# envelope_follower_1.net
KiCad netlist of a schematic drawn in EAGLE
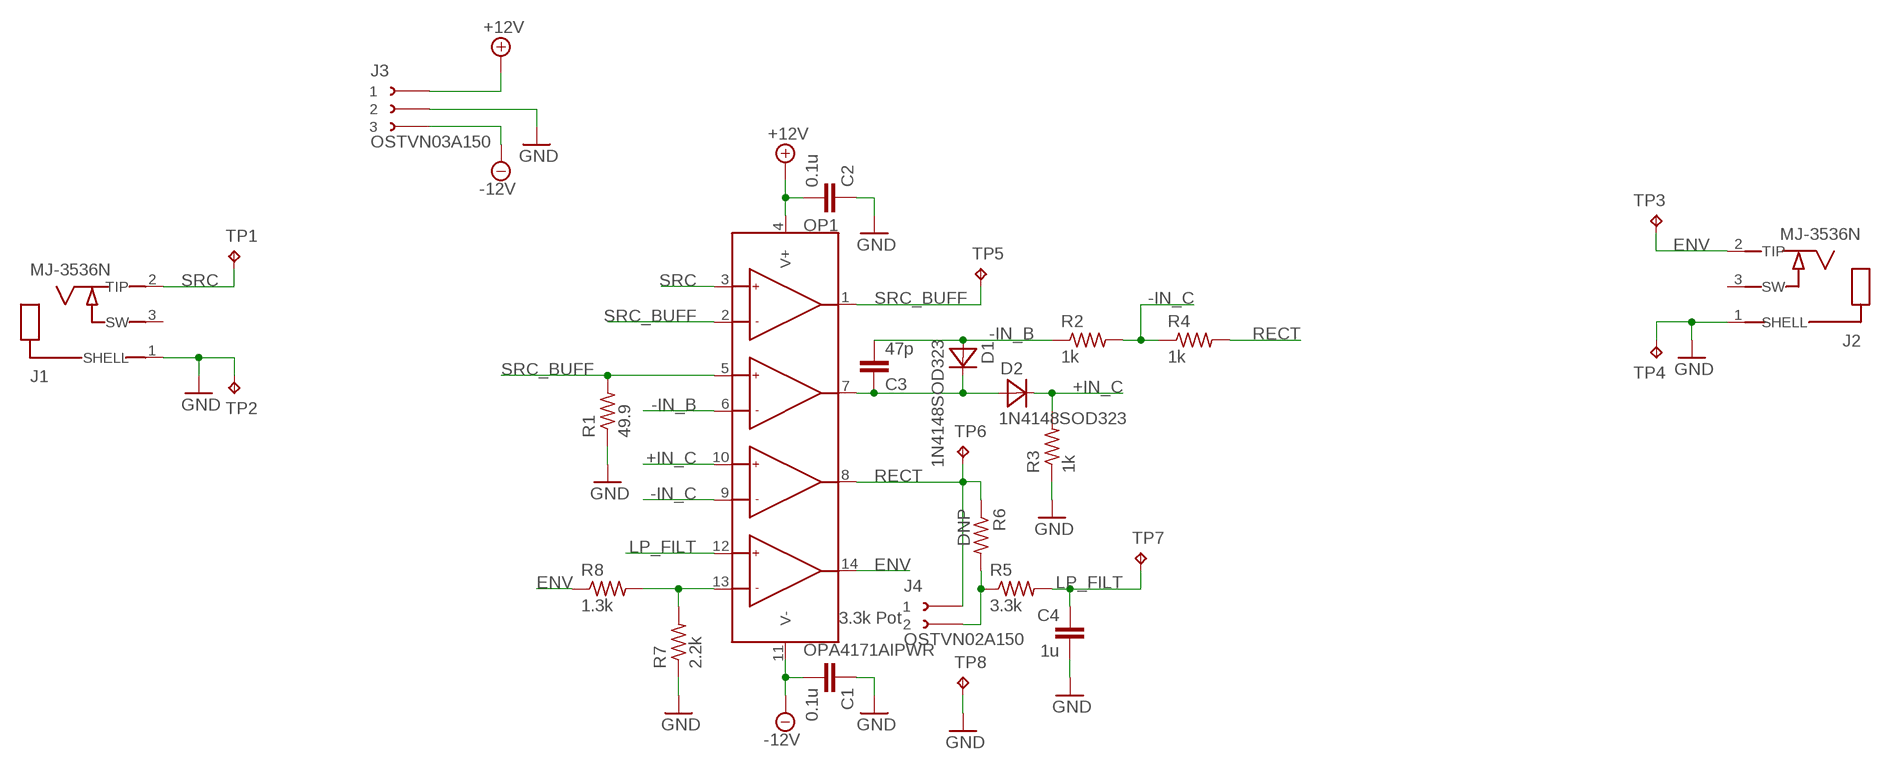
[diagram p0: schematic, sheet 1]

(export (version "E")
  (design (tool "Eeschema 10.0.6"))
  (components
    (comp (ref "C1")
      (value "0.1u")
      (footprint "eagle-import:C0603")
      (libsource (lib "eagle-import") (part "CAP-CER-SMD0603"))
    )
    (comp (ref "C2")
      (value "0.1u")
      (footprint "eagle-import:C0603")
      (libsource (lib "eagle-import") (part "CAP-CER-SMD0603"))
    )
    (comp (ref "C3")
      (value "47p")
      (footprint "eagle-import:C0603")
      (libsource (lib "eagle-import") (part "CAP-CER-SMD0603"))
    )
    (comp (ref "C4")
      (value "1u")
      (footprint "eagle-import:C0603")
      (libsource (lib "eagle-import") (part "CAP-CER-SMD0603"))
    )
    (comp (ref "D1")
      (value "1N4148SOD323")
      (footprint "eagle-import:SOD323")
      (libsource (lib "eagle-import") (part "1N4148SOD323"))
    )
    (comp (ref "D2")
      (value "1N4148SOD323")
      (footprint "eagle-import:SOD323")
      (libsource (lib "eagle-import") (part "1N4148SOD323"))
    )
    (comp (ref "J1")
      (value "MJ-3536N")
      (footprint "eagle-import:MJ-3536N")
      (libsource (lib "eagle-import") (part "MJ-3536N"))
    )
    (comp (ref "J2")
      (value "MJ-3536N")
      (footprint "eagle-import:MJ-3536N")
      (libsource (lib "eagle-import") (part "MJ-3536N"))
    )
    (comp (ref "J3")
      (value "OSTVN03A150")
      (footprint "eagle-import:OSTVN03A150")
      (libsource (lib "eagle-import") (part "OSTVN03A150"))
    )
    (comp (ref "J4")
      (value "OSTVN02A150")
      (footprint "eagle-import:OSTVN02A150")
      (libsource (lib "eagle-import") (part "OSTVN02A150"))
    )
    (comp (ref "OP1")
      (value "OPA4171AIPWR")
      (footprint "eagle-import:SOP65P640X120-14")
      (libsource (lib "eagle-import") (part "OPA4171AIPWR"))
    )
    (comp (ref "R1")
      (value "49.9")
      (footprint "eagle-import:R0603")
      (libsource (lib "eagle-import") (part "RES-SMD0603"))
    )
    (comp (ref "R2")
      (value "1k")
      (footprint "eagle-import:R0603")
      (libsource (lib "eagle-import") (part "RES-SMD0603"))
    )
    (comp (ref "R3")
      (value "1k")
      (footprint "eagle-import:R0603")
      (libsource (lib "eagle-import") (part "RES-SMD0603"))
    )
    (comp (ref "R4")
      (value "1k")
      (footprint "eagle-import:R0603")
      (libsource (lib "eagle-import") (part "RES-SMD0603"))
    )
    (comp (ref "R5")
      (value "3.3k")
      (footprint "eagle-import:R0603")
      (libsource (lib "eagle-import") (part "RES-SMD0603"))
    )
    (comp (ref "R6")
      (value "DNP")
      (footprint "eagle-import:R0603")
      (libsource (lib "eagle-import") (part "RES-SMD0603"))
    )
    (comp (ref "R7")
      (value "2.2k")
      (footprint "eagle-import:R0603")
      (libsource (lib "eagle-import") (part "RES-SMD0603"))
    )
    (comp (ref "R8")
      (value "1.3k")
      (footprint "eagle-import:R0603")
      (libsource (lib "eagle-import") (part "RES-SMD0603"))
    )
    (comp (ref "TP1")
      (value "TP_THM_1.6_S")
      (footprint "eagle-import:TP_THM_1.6_S")
      (libsource (lib "eagle-import") (part "TP_THM_1.6_S"))
    )
    (comp (ref "TP2")
      (value "TP_THM_1.6_S")
      (footprint "eagle-import:TP_THM_1.6_S")
      (libsource (lib "eagle-import") (part "TP_THM_1.6_S"))
    )
    (comp (ref "TP3")
      (value "TP_THM_1.6_S")
      (footprint "eagle-import:TP_THM_1.6_S")
      (libsource (lib "eagle-import") (part "TP_THM_1.6_S"))
    )
    (comp (ref "TP4")
      (value "TP_THM_1.6_S")
      (footprint "eagle-import:TP_THM_1.6_S")
      (libsource (lib "eagle-import") (part "TP_THM_1.6_S"))
    )
    (comp (ref "TP5")
      (value "TP_THM_1.6_S")
      (footprint "eagle-import:TP_THM_1.6_S")
      (libsource (lib "eagle-import") (part "TP_THM_1.6_S"))
    )
    (comp (ref "TP6")
      (value "TP_THM_1.6_S")
      (footprint "eagle-import:TP_THM_1.6_S")
      (libsource (lib "eagle-import") (part "TP_THM_1.6_S"))
    )
    (comp (ref "TP7")
      (value "TP_THM_1.6_S")
      (footprint "eagle-import:TP_THM_1.6_S")
      (libsource (lib "eagle-import") (part "TP_THM_1.6_S"))
    )
    (comp (ref "TP8")
      (value "TP_THM_1.6_S")
      (footprint "eagle-import:TP_THM_1.6_S")
      (libsource (lib "eagle-import") (part "TP_THM_1.6_S"))
    )
  )
  (nets
    (net (code "1") (name "+12V") (class "Default")
      (node (ref "C2") (pin "2") (pinfunction "2_2") (pintype "passive"))
      (node (ref "J3") (pin "P$1") (pinfunction "1_P$1") (pintype "passive"))
      (node (ref "OP1") (pin "4") (pinfunction "V+_4") (pintype "bidirectional"))
    )
    (net (code "2") (name "-12V") (class "Default")
      (node (ref "C1") (pin "2") (pinfunction "2_2") (pintype "passive"))
      (node (ref "J3") (pin "P$3") (pinfunction "3_P$3") (pintype "passive"))
      (node (ref "OP1") (pin "11") (pinfunction "V-_11") (pintype "bidirectional"))
    )
    (net (code "3") (name "/+IN_C") (class "Default")
      (node (ref "D2") (pin "C") (pinfunction "C_C") (pintype "passive"))
      (node (ref "OP1") (pin "10") (pinfunction "+IN_C_10") (pintype "bidirectional"))
      (node (ref "R3") (pin "2") (pinfunction "2_2") (pintype "passive"))
    )
    (net (code "4") (name "/-IN_B") (class "Default")
      (node (ref "C3") (pin "2") (pinfunction "2_2") (pintype "passive"))
      (node (ref "D1") (pin "A") (pinfunction "A_A") (pintype "passive"))
      (node (ref "OP1") (pin "6") (pinfunction "-IN_B_6") (pintype "bidirectional"))
      (node (ref "R2") (pin "1") (pinfunction "1_1") (pintype "passive"))
    )
    (net (code "5") (name "/-IN_C") (class "Default")
      (node (ref "OP1") (pin "9") (pinfunction "-IN_C_9") (pintype "bidirectional"))
      (node (ref "R2") (pin "2") (pinfunction "2_2") (pintype "passive"))
      (node (ref "R4") (pin "1") (pinfunction "1_1") (pintype "passive"))
    )
    (net (code "6") (name "/ENV") (class "Default")
      (node (ref "J2") (pin "2") (pinfunction "TIP_2") (pintype "bidirectional"))
      (node (ref "OP1") (pin "14") (pinfunction "OUT_D_14") (pintype "bidirectional"))
      (node (ref "R8") (pin "1") (pinfunction "1_1") (pintype "passive"))
      (node (ref "TP3") (pin "P$1") (pinfunction "TP_P$1") (pintype "input"))
    )
    (net (code "7") (name "/LP_FILT") (class "Default")
      (node (ref "C4") (pin "1") (pinfunction "1_1") (pintype "passive"))
      (node (ref "OP1") (pin "12") (pinfunction "+IN_D_12") (pintype "bidirectional"))
      (node (ref "R5") (pin "2") (pinfunction "2_2") (pintype "passive"))
      (node (ref "TP7") (pin "P$1") (pinfunction "TP_P$1") (pintype "input"))
    )
    (net (code "8") (name "/RECT") (class "Default")
      (node (ref "J4") (pin "P$1") (pinfunction "1_P$1") (pintype "passive"))
      (node (ref "OP1") (pin "8") (pinfunction "OUT_C_8") (pintype "bidirectional"))
      (node (ref "R4") (pin "2") (pinfunction "2_2") (pintype "passive"))
      (node (ref "R6") (pin "1") (pinfunction "1_1") (pintype "passive"))
      (node (ref "TP6") (pin "P$1") (pinfunction "TP_P$1") (pintype "input"))
    )
    (net (code "9") (name "/SRC") (class "Default")
      (node (ref "J1") (pin "2") (pinfunction "TIP_2") (pintype "bidirectional"))
      (node (ref "OP1") (pin "3") (pinfunction "+IN_A_3") (pintype "bidirectional"))
      (node (ref "TP1") (pin "P$1") (pinfunction "TP_P$1") (pintype "input"))
    )
    (net (code "10") (name "/SRC_BUFF") (class "Default")
      (node (ref "OP1") (pin "1") (pinfunction "OUT_A_1") (pintype "bidirectional"))
      (node (ref "OP1") (pin "2") (pinfunction "-IN_A_2") (pintype "bidirectional"))
      (node (ref "OP1") (pin "5") (pinfunction "+IN_B_5") (pintype "bidirectional"))
      (node (ref "R1") (pin "2") (pinfunction "2_2") (pintype "passive"))
      (node (ref "TP5") (pin "P$1") (pinfunction "TP_P$1") (pintype "input"))
    )
    (net (code "11") (name "GND") (class "Default")
      (node (ref "C1") (pin "1") (pinfunction "1_1") (pintype "passive"))
      (node (ref "C2") (pin "1") (pinfunction "1_1") (pintype "passive"))
      (node (ref "C4") (pin "2") (pinfunction "2_2") (pintype "passive"))
      (node (ref "J1") (pin "1") (pinfunction "SHELL_1") (pintype "bidirectional"))
      (node (ref "J2") (pin "1") (pinfunction "SHELL_1") (pintype "bidirectional"))
      (node (ref "J3") (pin "P$2") (pinfunction "2_P$2") (pintype "passive"))
      (node (ref "R1") (pin "1") (pinfunction "1_1") (pintype "passive"))
      (node (ref "R3") (pin "1") (pinfunction "1_1") (pintype "passive"))
      (node (ref "R7") (pin "1") (pinfunction "1_1") (pintype "passive"))
      (node (ref "TP2") (pin "P$1") (pinfunction "TP_P$1") (pintype "input"))
      (node (ref "TP4") (pin "P$1") (pinfunction "TP_P$1") (pintype "input"))
      (node (ref "TP8") (pin "P$1") (pinfunction "TP_P$1") (pintype "input"))
    )
    (net (code "12") (name "Net-(J4-2)") (class "Default")
      (node (ref "J4") (pin "P$2") (pinfunction "2_P$2") (pintype "passive"))
      (node (ref "R5") (pin "1") (pinfunction "1_1") (pintype "passive"))
      (node (ref "R6") (pin "2") (pinfunction "2_2") (pintype "passive"))
    )
    (net (code "13") (name "Net-(OP1--IN_D)") (class "Default")
      (node (ref "OP1") (pin "13") (pinfunction "-IN_D_13") (pintype "bidirectional"))
      (node (ref "R7") (pin "2") (pinfunction "2_2") (pintype "passive"))
      (node (ref "R8") (pin "2") (pinfunction "2_2") (pintype "passive"))
    )
    (net (code "14") (name "Net-(OP1-OUT_B)") (class "Default")
      (node (ref "C3") (pin "1") (pinfunction "1_1") (pintype "passive"))
      (node (ref "D1") (pin "C") (pinfunction "C_C") (pintype "passive"))
      (node (ref "D2") (pin "A") (pinfunction "A_A") (pintype "passive"))
      (node (ref "OP1") (pin "7") (pinfunction "OUT_B_7") (pintype "bidirectional"))
    )
    (net (code "15") (name "unconnected-(J1-SW-Pad3)") (class "Default")
      (node (ref "J1") (pin "3") (pinfunction "SW_3") (pintype "bidirectional"))
    )
    (net (code "16") (name "unconnected-(J2-SW-Pad3)") (class "Default")
      (node (ref "J2") (pin "3") (pinfunction "SW_3") (pintype "bidirectional"))
    )
  )
)
